# Interfaces.net
KiCad netlist of a schematic drawn in Altium Designer
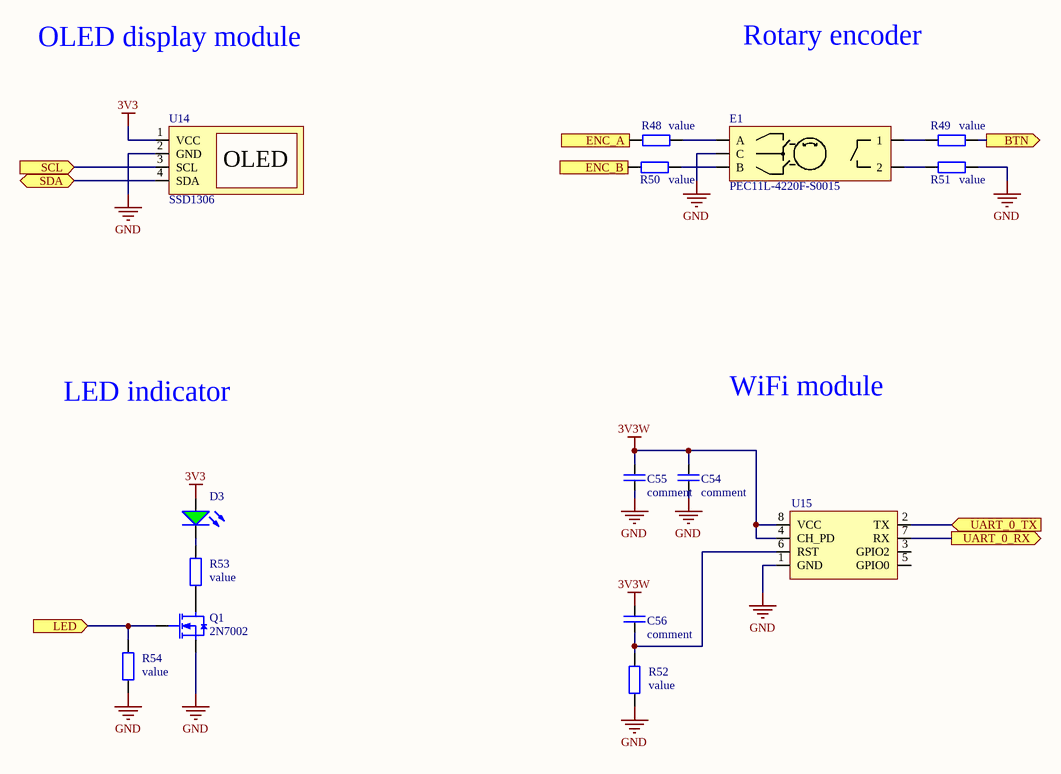
[diagram p0: Interfaces.SchDoc]

(export (version "E")
  (design (tool "Eeschema 10.0.6"))
  (components
    (comp (ref "C54")
      (value "comment")
      (footprint "C_0603")
      (description "Generic capacitor")
      (libsource (lib "DAQ") (part "Capacitor"))
    )
    (comp (ref "C55")
      (value "comment")
      (footprint "C_0603")
      (description "Generic capacitor")
      (libsource (lib "DAQ") (part "Capacitor"))
    )
    (comp (ref "C56")
      (value "comment")
      (footprint "C_0603")
      (description "Generic capacitor")
      (libsource (lib "DAQ") (part "Capacitor"))
    )
    (comp (ref "D3")
      (value "LED Green")
      (footprint "LED_0603")
      (description "Generic LED Green")
      (libsource (lib "DAQ") (part "LED Green"))
    )
    (comp (ref "E1")
      (value "PEC11L-4220F-S0015")
      (footprint "PEC11L-4220F-S0015")
      (description "Low Profile Encoder 15 PPR 2 Bit Quadrature 5VDC at 10 mA IP40 PCB Mount")
      (fields (field (name "MANUFACTURER") "BOURNS"))
      (libsource (lib "DAQ") (part "PEC11L-4220F-S0015"))
    )
    (comp (ref "Q1")
      (value "2N7002")
      (footprint "SOT23-3")
      (description "Power MOSFET, N Channel, 60 V, 300 mA, 2.8 ohm, SOT-23, Surface Mount")
      (fields (field (name "MANUFACTURER") "NXP"))
      (libsource (lib "DAQ") (part "2N7002"))
    )
    (comp (ref "R48")
      (value "value")
      (footprint "R_0603")
      (description "Generic resistor")
      (fields (field (name "Comment") "comment"))
      (libsource (lib "DAQ") (part "Resistor"))
    )
    (comp (ref "R49")
      (value "value")
      (footprint "R_0603")
      (description "Generic resistor")
      (fields (field (name "Comment") "comment"))
      (libsource (lib "DAQ") (part "Resistor"))
    )
    (comp (ref "R50")
      (value "value")
      (footprint "R_0603")
      (description "Generic resistor")
      (fields (field (name "Comment") "comment"))
      (libsource (lib "DAQ") (part "Resistor"))
    )
    (comp (ref "R51")
      (value "value")
      (footprint "R_0603")
      (description "Generic resistor")
      (fields (field (name "Comment") "comment"))
      (libsource (lib "DAQ") (part "Resistor"))
    )
    (comp (ref "R52")
      (value "value")
      (footprint "R_0603")
      (description "Generic resistor")
      (fields (field (name "Comment") "comment"))
      (libsource (lib "DAQ") (part "Resistor"))
    )
    (comp (ref "R53")
      (value "value")
      (footprint "R_0603")
      (description "Generic resistor")
      (fields (field (name "Comment") "comment"))
      (libsource (lib "DAQ") (part "Resistor"))
    )
    (comp (ref "R54")
      (value "value")
      (footprint "R_0603")
      (description "Generic resistor")
      (fields (field (name "Comment") "comment"))
      (libsource (lib "DAQ") (part "Resistor"))
    )
    (comp (ref "U14")
      (value "SSD1306")
      (footprint "OLED1")
      (description "OLED display module")
      (libsource (lib "DAQ") (part "OLED_SSD1306"))
    )
    (comp (ref "U15")
      (value "ESP-01")
      (footprint "ESP-01")
      (description "WIFI module")
      (libsource (lib "DAQ") (part "ESP-01"))
    )
  )
  (nets
    (net (code "1") (name "/BTN") (class "Default") (node (ref "R49") (pin "2") (pintype "passive")))
    (net (code "2") (name "/ENC_A") (class "Default") (node (ref "R48") (pin "1") (pintype "passive")))
    (net (code "3") (name "/ENC_B") (class "Default") (node (ref "R50") (pin "1") (pintype "passive")))
    (net (code "4") (name "/LED") (class "Default")
      (node (ref "Q1") (pin "1") (pinfunction "G_1") (pintype "passive"))
      (node (ref "R54") (pin "2") (pintype "passive"))
    )
    (net (code "5") (name "/SCL") (class "Default")
      (node (ref "U14") (pin "3") (pinfunction "SCL_3") (pintype "passive"))
    )
    (net (code "6") (name "/SDA") (class "Default")
      (node (ref "U14") (pin "4") (pinfunction "SDA_4") (pintype "passive"))
    )
    (net (code "7") (name "/UART_0_RX") (class "Default")
      (node (ref "U15") (pin "7") (pinfunction "RX_7") (pintype "passive"))
    )
    (net (code "8") (name "/UART_0_TX") (class "Default")
      (node (ref "U15") (pin "2") (pinfunction "TX_2") (pintype "passive"))
    )
    (net (code "9") (name "3V3") (class "Default")
      (node (ref "D3") (pin "2") (pinfunction "+_2") (pintype "passive"))
      (node (ref "U14") (pin "1") (pinfunction "VCC_1") (pintype "passive"))
    )
    (net (code "10") (name "3V3W") (class "Default")
      (node (ref "C54") (pin "2") (pinfunction "2_2") (pintype "passive"))
      (node (ref "C55") (pin "2") (pinfunction "2_2") (pintype "passive"))
      (node (ref "C56") (pin "2") (pinfunction "2_2") (pintype "passive"))
      (node (ref "U15") (pin "4") (pinfunction "CH_PD_4") (pintype "passive"))
      (node (ref "U15") (pin "8") (pinfunction "VCC_8") (pintype "passive"))
    )
    (net (code "11") (name "GND") (class "Default")
      (node (ref "C54") (pin "1") (pinfunction "1_1") (pintype "passive"))
      (node (ref "C55") (pin "1") (pinfunction "1_1") (pintype "passive"))
      (node (ref "E1") (pin "C") (pinfunction "C_C") (pintype "passive"))
      (node (ref "Q1") (pin "2") (pinfunction "S_2") (pintype "passive"))
      (node (ref "R51") (pin "2") (pintype "passive"))
      (node (ref "R52") (pin "1") (pintype "passive"))
      (node (ref "R54") (pin "1") (pintype "passive"))
      (node (ref "U14") (pin "2") (pinfunction "GND_2") (pintype "passive"))
      (node (ref "U15") (pin "1") (pinfunction "GND_1") (pintype "passive"))
    )
    (net (code "12") (name "Net-(D3--)") (class "Default")
      (node (ref "D3") (pin "1") (pinfunction "-_1") (pintype "passive"))
      (node (ref "R53") (pin "2") (pintype "passive"))
    )
    (net (code "13") (name "Net-(E1-Pad1)") (class "Default")
      (node (ref "E1") (pin "1") (pinfunction "1_1") (pintype "passive"))
      (node (ref "R49") (pin "1") (pintype "passive"))
    )
    (net (code "14") (name "Net-(E1-Pad2)") (class "Default")
      (node (ref "E1") (pin "2") (pinfunction "2_2") (pintype "passive"))
      (node (ref "R51") (pin "1") (pintype "passive"))
    )
    (net (code "15") (name "Net-(E1-PadA)") (class "Default")
      (node (ref "E1") (pin "A") (pinfunction "A_A") (pintype "passive"))
      (node (ref "R48") (pin "2") (pintype "passive"))
    )
    (net (code "16") (name "Net-(E1-PadB)") (class "Default")
      (node (ref "E1") (pin "B") (pinfunction "B_B") (pintype "passive"))
      (node (ref "R50") (pin "2") (pintype "passive"))
    )
    (net (code "17") (name "Net-(Q1-D)") (class "Default")
      (node (ref "Q1") (pin "3") (pinfunction "D_3") (pintype "passive"))
      (node (ref "R53") (pin "1") (pintype "passive"))
    )
    (net (code "18") (name "Net-(U15-RST)") (class "Default")
      (node (ref "C56") (pin "1") (pinfunction "1_1") (pintype "passive"))
      (node (ref "R52") (pin "2") (pintype "passive"))
      (node (ref "U15") (pin "6") (pinfunction "RST_6") (pintype "passive"))
    )
    (net (code "19") (name "unconnected-(U15-GPIO0-Pad5)") (class "Default")
      (node (ref "U15") (pin "5") (pinfunction "GPIO0_5") (pintype "passive"))
    )
    (net (code "20") (name "unconnected-(U15-GPIO2-Pad3)") (class "Default")
      (node (ref "U15") (pin "3") (pinfunction "GPIO2_3") (pintype "passive"))
    )
  )
)
